# MCB-Laird-BL652-v2_0_0.net
KiCad netlist of a schematic drawn in EAGLE
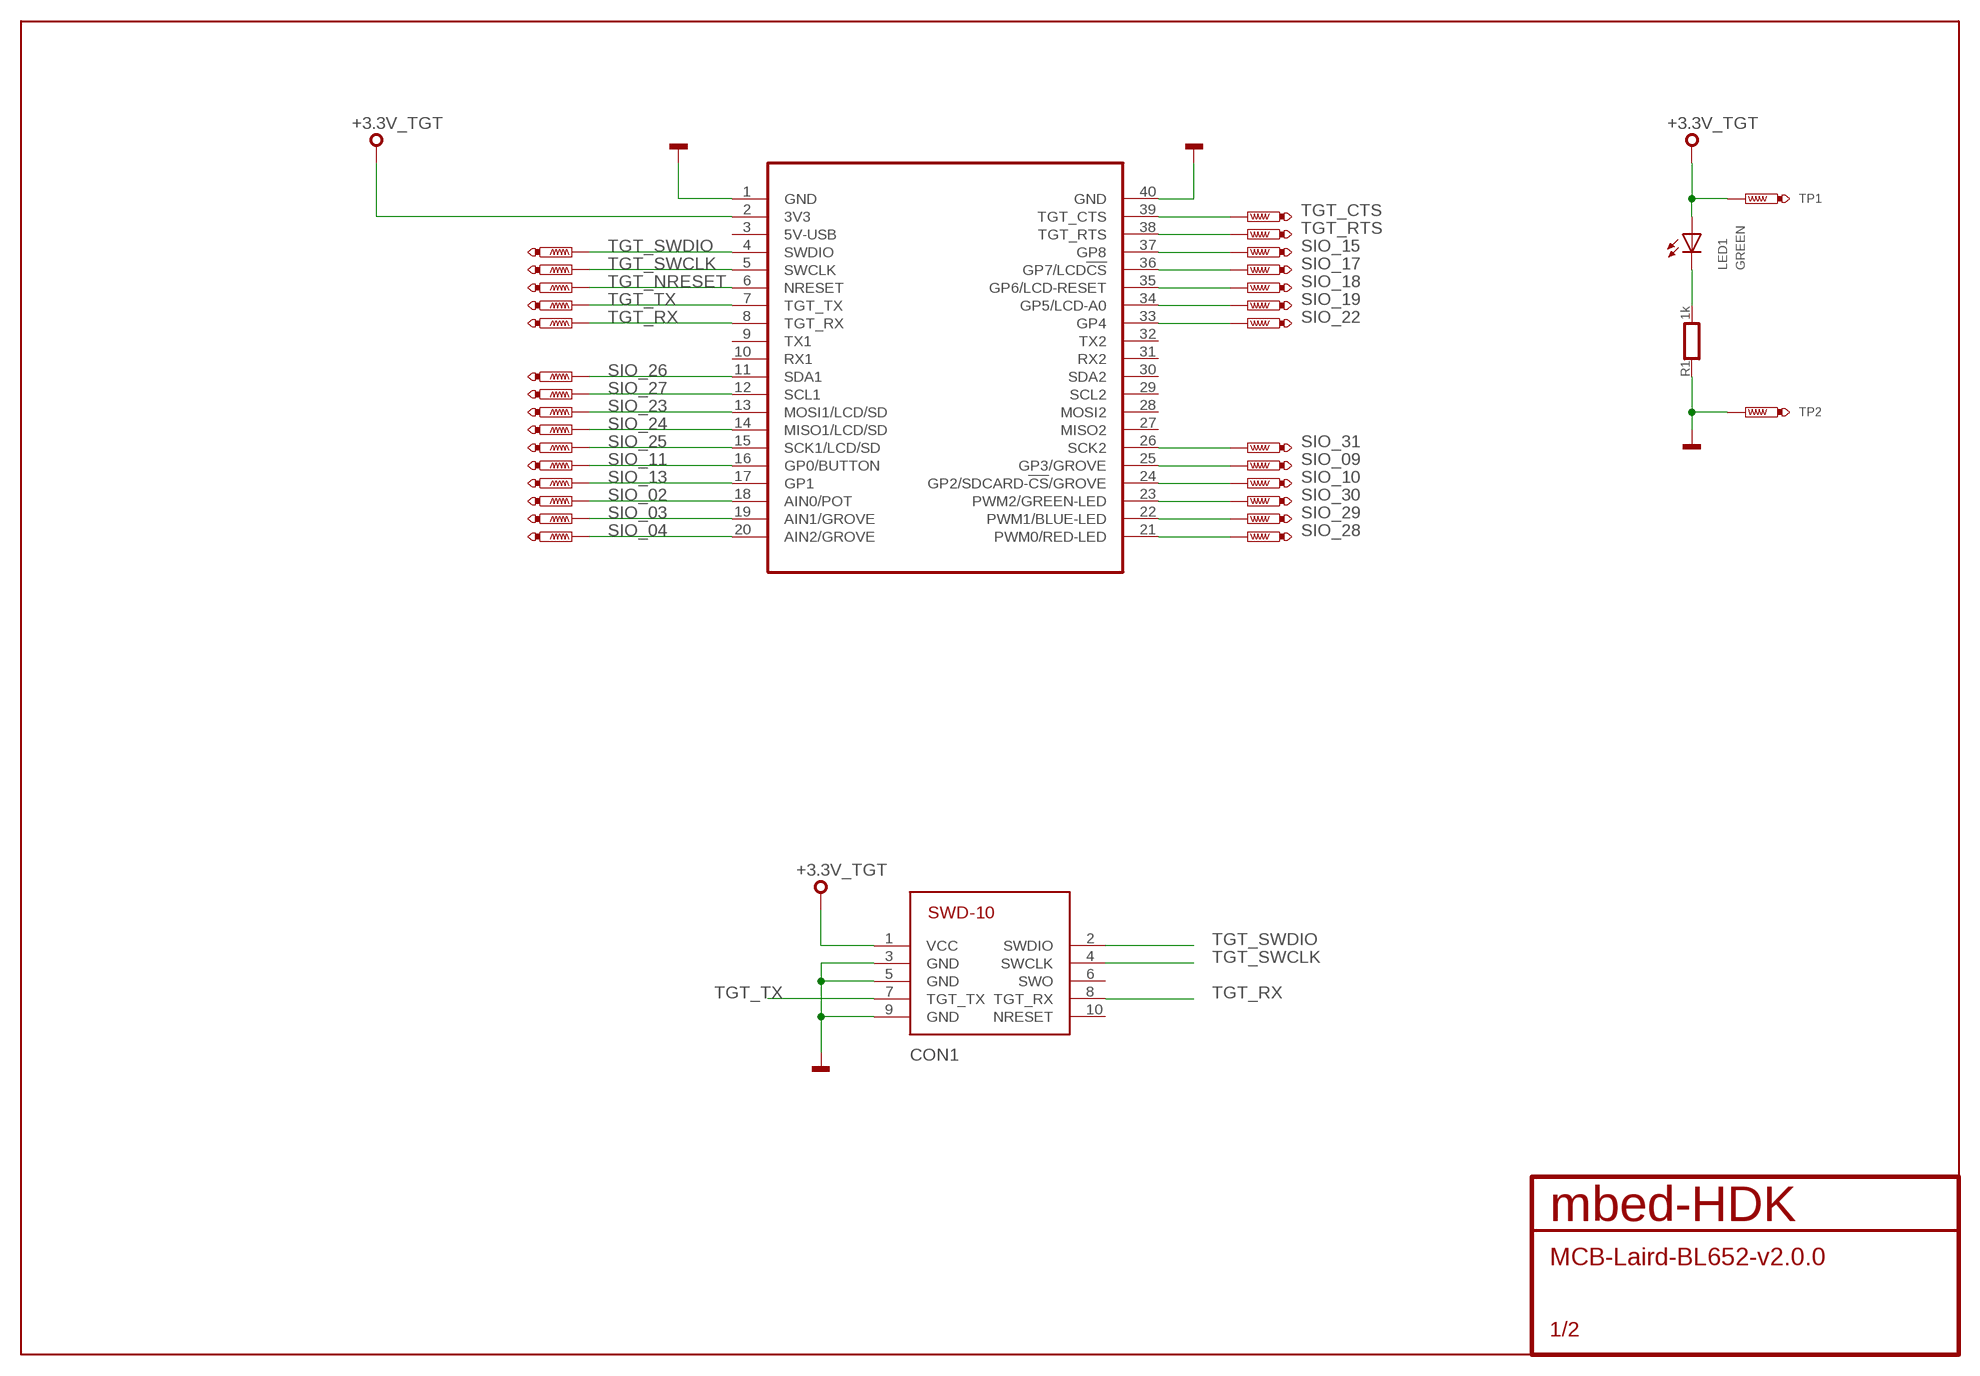
[diagram p0: schematic, sheet 1]
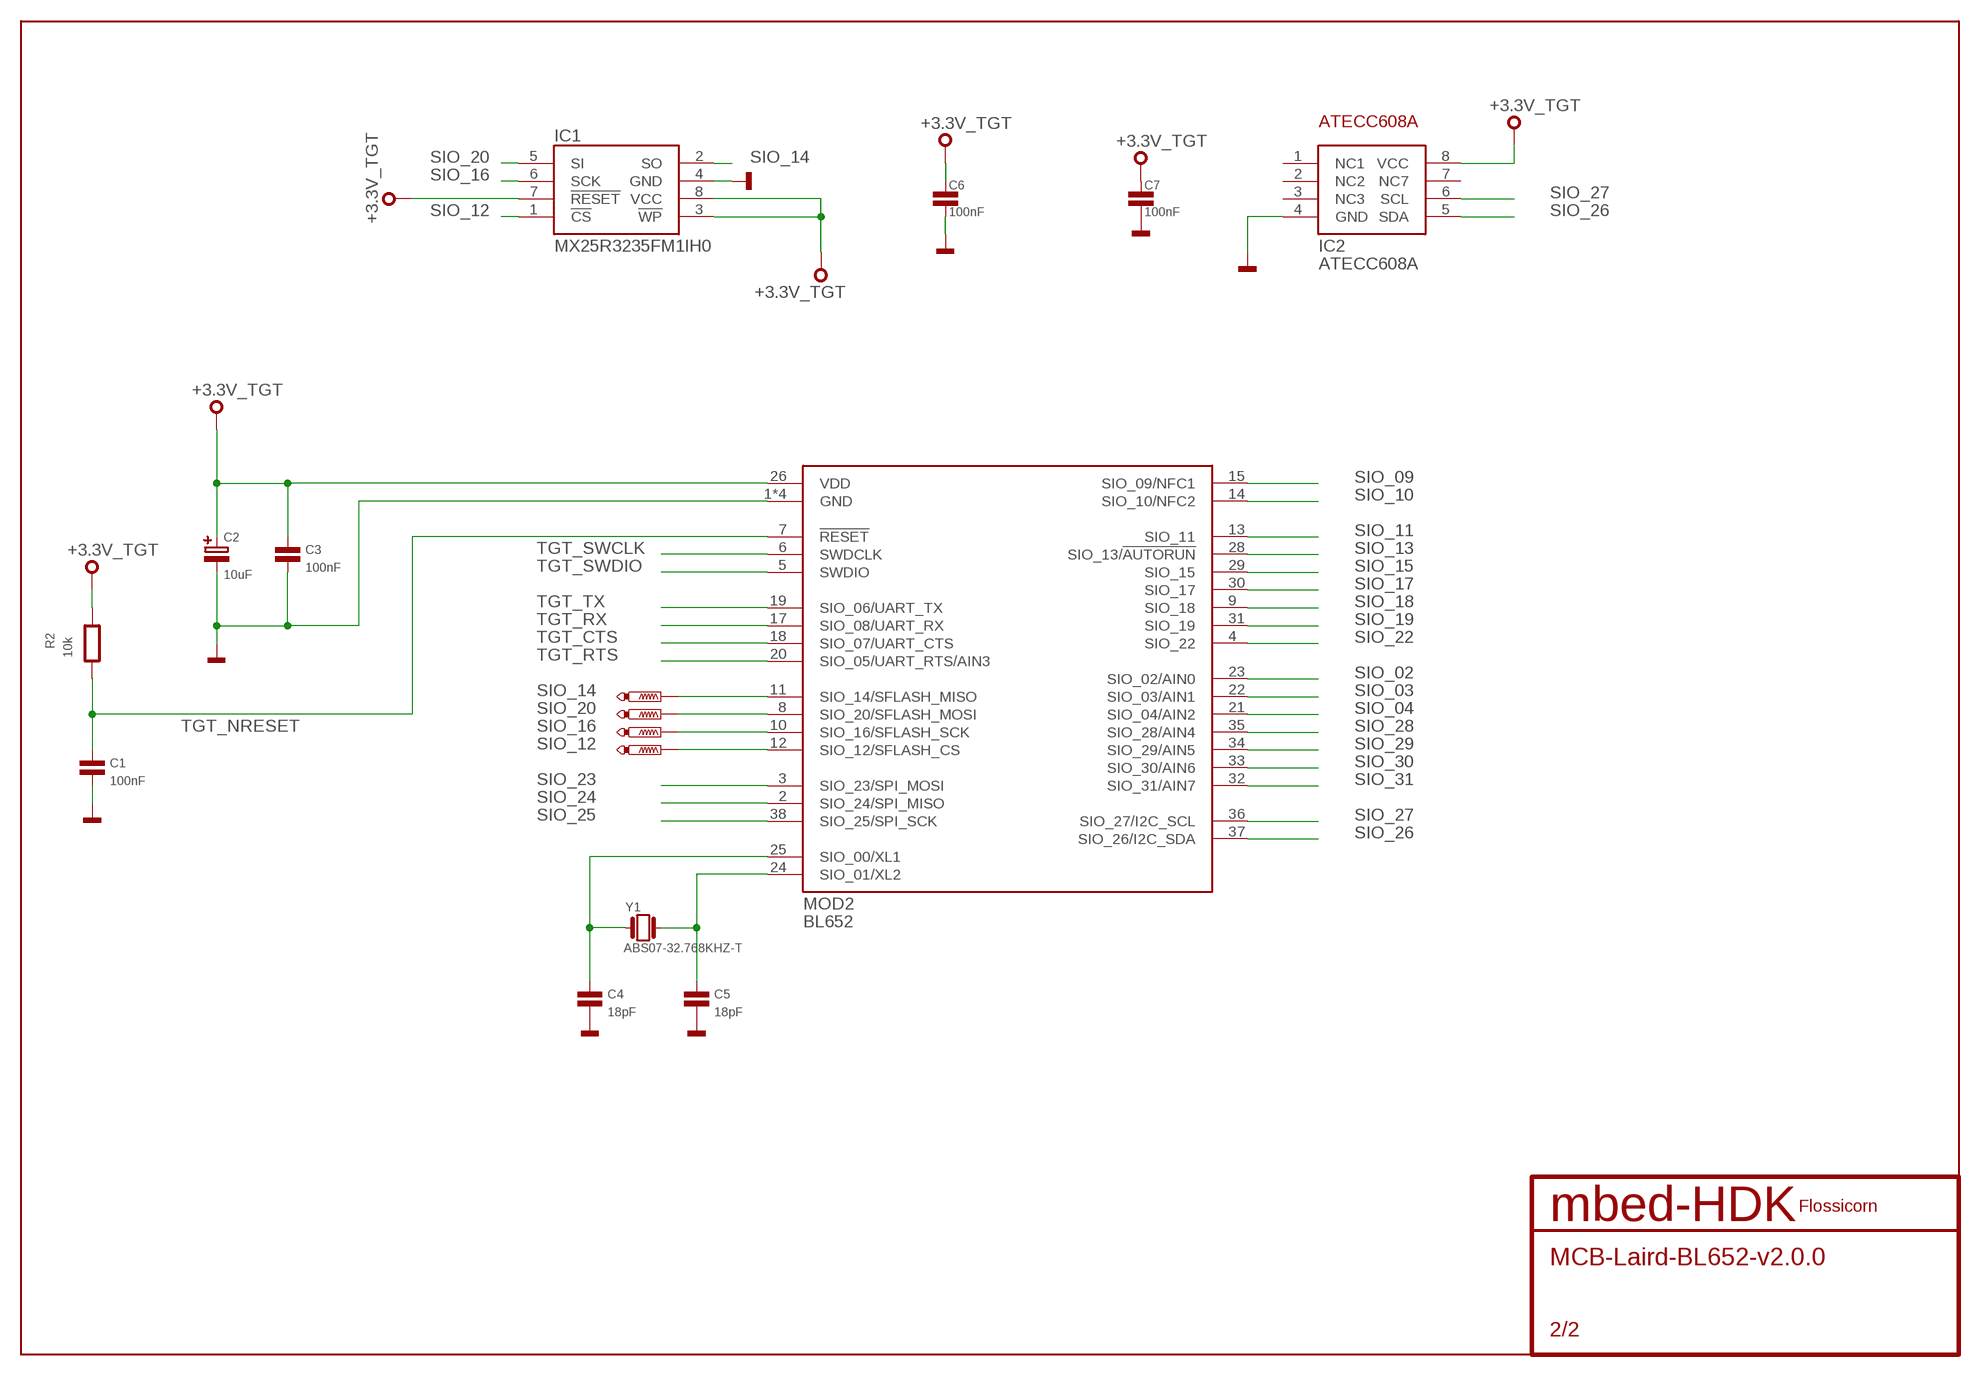
[diagram p1: schematic, sheet 2]

(export (version "E")
  (design (tool "Eeschema 10.0.6"))
  (components
    (comp (ref "CON1")
      (value "SWD-10/TC2050_SMD")
      (footprint "eagle-import:FTSH-105-02")
      (libsource (lib "eagle-import") (part "SWD-10/TC2050_SMD"))
    )
    (comp (ref "LED1")
      (value "GREEN")
      (footprint "eagle-import:CHIPLED_0603")
      (fields (field (name "MF") "Wurth Electronics Inc"))
      (libsource (lib "eagle-import") (part "SMD_LED0603"))
    )
    (comp (ref "MOD1")
      (value "MODULE_DAUGHTER")
      (footprint "eagle-import:MODULE_DAUGHTER")
      (libsource (lib "eagle-import") (part "MODULE_DAUGHTER"))
    )
    (comp (ref "R1")
      (value "1k")
      (footprint "eagle-import:0603")
      (libsource (lib "eagle-import") (part "RESISTOR0603"))
    )
    (comp (ref "TP1")
      (value "TEST-POINT-50R-PTH")
      (footprint "eagle-import:TP50-PTH")
      (libsource (lib "eagle-import") (part "TEST-POINT-50R-PTH"))
    )
    (comp (ref "TP2")
      (value "TEST-POINT-50R-PTH")
      (footprint "eagle-import:TP50-PTH")
      (libsource (lib "eagle-import") (part "TEST-POINT-50R-PTH"))
    )
    (comp (ref "TP3")
      (value "PTR1TP07R")
      (footprint "eagle-import:TP07R")
      (libsource (lib "eagle-import") (part "PTR1TP07R"))
    )
    (comp (ref "TP4")
      (value "PTR1TP07R")
      (footprint "eagle-import:TP07R")
      (libsource (lib "eagle-import") (part "PTR1TP07R"))
    )
    (comp (ref "TP5")
      (value "PTR1TP07R")
      (footprint "eagle-import:TP07R")
      (libsource (lib "eagle-import") (part "PTR1TP07R"))
    )
    (comp (ref "TP6")
      (value "PTR1TP07R")
      (footprint "eagle-import:TP07R")
      (libsource (lib "eagle-import") (part "PTR1TP07R"))
    )
    (comp (ref "TP7")
      (value "PTR1TP07R")
      (footprint "eagle-import:TP07R")
      (libsource (lib "eagle-import") (part "PTR1TP07R"))
    )
    (comp (ref "TP8")
      (value "PTR1TP07R")
      (footprint "eagle-import:TP07R")
      (libsource (lib "eagle-import") (part "PTR1TP07R"))
    )
    (comp (ref "TP9")
      (value "PTR1TP07R")
      (footprint "eagle-import:TP07R")
      (libsource (lib "eagle-import") (part "PTR1TP07R"))
    )
    (comp (ref "TP10")
      (value "PTR1TP07R")
      (footprint "eagle-import:TP07R")
      (libsource (lib "eagle-import") (part "PTR1TP07R"))
    )
    (comp (ref "TP11")
      (value "PTR1TP07R")
      (footprint "eagle-import:TP07R")
      (libsource (lib "eagle-import") (part "PTR1TP07R"))
    )
    (comp (ref "TP12")
      (value "PTR1TP07R")
      (footprint "eagle-import:TP07R")
      (libsource (lib "eagle-import") (part "PTR1TP07R"))
    )
    (comp (ref "TP13")
      (value "PTR1TP07R")
      (footprint "eagle-import:TP07R")
      (libsource (lib "eagle-import") (part "PTR1TP07R"))
    )
    (comp (ref "TP14")
      (value "PTR1TP07R")
      (footprint "eagle-import:TP07R")
      (libsource (lib "eagle-import") (part "PTR1TP07R"))
    )
    (comp (ref "TP15")
      (value "PTR1TP07R")
      (footprint "eagle-import:TP07R")
      (libsource (lib "eagle-import") (part "PTR1TP07R"))
    )
    (comp (ref "TP16")
      (value "PTR1TP07R")
      (footprint "eagle-import:TP07R")
      (libsource (lib "eagle-import") (part "PTR1TP07R"))
    )
    (comp (ref "TP17")
      (value "PTR1TP07R")
      (footprint "eagle-import:TP07R")
      (libsource (lib "eagle-import") (part "PTR1TP07R"))
    )
    (comp (ref "TP18")
      (value "PTR1TP07R")
      (footprint "eagle-import:TP07R")
      (libsource (lib "eagle-import") (part "PTR1TP07R"))
    )
    (comp (ref "TP19")
      (value "PTR1TP07R")
      (footprint "eagle-import:TP07R")
      (libsource (lib "eagle-import") (part "PTR1TP07R"))
    )
    (comp (ref "TP20")
      (value "PTR1TP07R")
      (footprint "eagle-import:TP07R")
      (libsource (lib "eagle-import") (part "PTR1TP07R"))
    )
    (comp (ref "TP21")
      (value "PTR1TP07R")
      (footprint "eagle-import:TP07R")
      (libsource (lib "eagle-import") (part "PTR1TP07R"))
    )
    (comp (ref "TP22")
      (value "PTR1TP07R")
      (footprint "eagle-import:TP07R")
      (libsource (lib "eagle-import") (part "PTR1TP07R"))
    )
    (comp (ref "TP23")
      (value "PTR1TP07R")
      (footprint "eagle-import:TP07R")
      (libsource (lib "eagle-import") (part "PTR1TP07R"))
    )
    (comp (ref "TP24")
      (value "PTR1TP07R")
      (footprint "eagle-import:TP07R")
      (libsource (lib "eagle-import") (part "PTR1TP07R"))
    )
    (comp (ref "TP25")
      (value "PTR1TP07R")
      (footprint "eagle-import:TP07R")
      (libsource (lib "eagle-import") (part "PTR1TP07R"))
    )
    (comp (ref "TP26")
      (value "PTR1TP07R")
      (footprint "eagle-import:TP07R")
      (libsource (lib "eagle-import") (part "PTR1TP07R"))
    )
    (comp (ref "TP27")
      (value "PTR1TP07R")
      (footprint "eagle-import:TP07R")
      (libsource (lib "eagle-import") (part "PTR1TP07R"))
    )
    (comp (ref "TP28")
      (value "PTR1TP07R")
      (footprint "eagle-import:TP07R")
      (libsource (lib "eagle-import") (part "PTR1TP07R"))
    )
    (comp (ref "TP29")
      (value "PTR1TP07R")
      (footprint "eagle-import:TP07R")
      (libsource (lib "eagle-import") (part "PTR1TP07R"))
    )
    (comp (ref "TP30")
      (value "PTR1TP07R")
      (footprint "eagle-import:TP07R")
      (libsource (lib "eagle-import") (part "PTR1TP07R"))
    )
    (comp (ref "C1")
      (value "100nF")
      (footprint "eagle-import:0603")
      (libsource (lib "eagle-import") (part "C0603"))
    )
    (comp (ref "C2")
      (value "10uF")
      (footprint "eagle-import:SMC_B")
      (fields (field (name "MF") "Kemet"))
      (libsource (lib "eagle-import") (part "CAPACITOR-POLARISEDB"))
    )
    (comp (ref "C3")
      (value "100nF")
      (footprint "eagle-import:0603")
      (libsource (lib "eagle-import") (part "C0603"))
    )
    (comp (ref "C4")
      (value "18pF")
      (footprint "eagle-import:0603")
      (libsource (lib "eagle-import") (part "C0603"))
    )
    (comp (ref "C5")
      (value "18pF")
      (footprint "eagle-import:0603")
      (libsource (lib "eagle-import") (part "C0603"))
    )
    (comp (ref "C6")
      (value "100nF")
      (footprint "eagle-import:0603")
      (libsource (lib "eagle-import") (part "CAPACITOR0603"))
    )
    (comp (ref "C7")
      (value "100nF")
      (footprint "eagle-import:0603")
      (libsource (lib "eagle-import") (part "CAPACITOR0603"))
    )
    (comp (ref "IC1")
      (value "MX25R3235FM1IH0")
      (footprint "eagle-import:SO8")
      (fields (field (name "MF") "Macronix"))
      (libsource (lib "eagle-import") (part "MX25R3235FM1IH0"))
    )
    (comp (ref "IC2")
      (value "ATECC608A")
      (footprint "eagle-import:SO8")
      (fields (field (name "MF") "Atmel"))
      (libsource (lib "eagle-import") (part "ATECC608A"))
    )
    (comp (ref "MOD2")
      (value "BL652")
      (footprint "eagle-import:BL652")
      (fields (field (name "MF") "Laird"))
      (libsource (lib "eagle-import") (part "BL652"))
    )
    (comp (ref "R2")
      (value "10k")
      (footprint "eagle-import:0603")
      (libsource (lib "eagle-import") (part "RESISTOR0603"))
    )
    (comp (ref "SS1")
      (value "FLOSSICORN0.25")
      (footprint "eagle-import:FLOSSICORN-0.25")
      (libsource (lib "eagle-import") (part "FLOSSICORN0.25"))
    )
    (comp (ref "TP31")
      (value "PTR1TP07R")
      (footprint "eagle-import:TP07R")
      (libsource (lib "eagle-import") (part "PTR1TP07R"))
    )
    (comp (ref "TP32")
      (value "PTR1TP07R")
      (footprint "eagle-import:TP07R")
      (libsource (lib "eagle-import") (part "PTR1TP07R"))
    )
    (comp (ref "TP33")
      (value "PTR1TP07R")
      (footprint "eagle-import:TP07R")
      (libsource (lib "eagle-import") (part "PTR1TP07R"))
    )
    (comp (ref "TP34")
      (value "PTR1TP07R")
      (footprint "eagle-import:TP07R")
      (libsource (lib "eagle-import") (part "PTR1TP07R"))
    )
    (comp (ref "Y1")
      (value "ABS07-32.768KHZ-T")
      (footprint "eagle-import:FC135")
      (fields (field (name "MF") "Abracon"))
      (libsource (lib "eagle-import") (part "ABS07-32.768KHZ-T"))
    )
  )
  (nets
    (net (code "1") (name "+3.3V_TGT") (class "Default")
      (node (ref "C2") (pin "+") (pinfunction "+_+") (pintype "passive"))
      (node (ref "C3") (pin "1") (pinfunction "P$1_1") (pintype "passive"))
      (node (ref "C6") (pin "1") (pinfunction "P$1_1") (pintype "passive"))
      (node (ref "C7") (pin "1") (pinfunction "P$1_1") (pintype "passive"))
      (node (ref "CON1") (pin "1") (pinfunction "VCC_1") (pintype "bidirectional"))
      (node (ref "IC1") (pin "3") (pinfunction "~{WP}_3") (pintype "bidirectional"))
      (node (ref "IC1") (pin "7") (pinfunction "~{RESET}_7") (pintype "bidirectional"))
      (node (ref "IC1") (pin "8") (pinfunction "VCC_8") (pintype "bidirectional"))
      (node (ref "IC2") (pin "8") (pinfunction "VCC_8") (pintype "bidirectional"))
      (node (ref "LED1") (pin "A") (pinfunction "A_A") (pintype "passive"))
      (node (ref "MOD1") (pin "2") (pinfunction "3V3_2") (pintype "bidirectional"))
      (node (ref "MOD2") (pin "26") (pinfunction "VDD_26") (pintype "bidirectional"))
      (node (ref "R2") (pin "2") (pinfunction "P$2_2") (pintype "passive"))
      (node (ref "TP1") (pin "TP") (pinfunction "TP_TP") (pintype "input"))
    )
    (net (code "2") (name "GND") (class "Default")
      (node (ref "C1") (pin "2") (pinfunction "P$2_2") (pintype "passive"))
      (node (ref "C2") (pin "-") (pinfunction "-_-") (pintype "passive"))
      (node (ref "C3") (pin "2") (pinfunction "P$2_2") (pintype "passive"))
      (node (ref "C4") (pin "2") (pinfunction "P$2_2") (pintype "passive"))
      (node (ref "C5") (pin "2") (pinfunction "P$2_2") (pintype "passive"))
      (node (ref "C6") (pin "2") (pinfunction "P$2_2") (pintype "passive"))
      (node (ref "C7") (pin "2") (pinfunction "P$2_2") (pintype "passive"))
      (node (ref "CON1") (pin "3") (pinfunction "GND_3") (pintype "bidirectional"))
      (node (ref "CON1") (pin "5") (pinfunction "GND_5") (pintype "bidirectional"))
      (node (ref "CON1") (pin "9") (pinfunction "GND_9") (pintype "bidirectional"))
      (node (ref "IC1") (pin "4") (pinfunction "GND_4") (pintype "bidirectional"))
      (node (ref "IC2") (pin "4") (pinfunction "GND_4") (pintype "bidirectional"))
      (node (ref "MOD1") (pin "1") (pinfunction "GND_1") (pintype "bidirectional"))
      (node (ref "MOD1") (pin "40") (pinfunction "GND_40") (pintype "bidirectional"))
      (node (ref "MOD2") (pin "1") (pinfunction "GND_1") (pintype "bidirectional"))
      (node (ref "MOD2") (pin "16") (pinfunction "GND_16") (pintype "bidirectional"))
      (node (ref "MOD2") (pin "27") (pinfunction "GND_27") (pintype "bidirectional"))
      (node (ref "MOD2") (pin "39") (pinfunction "GND_39") (pintype "bidirectional"))
      (node (ref "R1") (pin "1") (pinfunction "P$1_1") (pintype "passive"))
      (node (ref "TP2") (pin "TP") (pinfunction "TP_TP") (pintype "input"))
    )
    (net (code "3") (name "Net-(C4-P$1)") (class "Default")
      (node (ref "C4") (pin "1") (pinfunction "P$1_1") (pintype "passive"))
      (node (ref "MOD2") (pin "25") (pinfunction "SIO_00/XL1_25") (pintype "bidirectional"))
      (node (ref "Y1") (pin "X1") (pinfunction "1_X1") (pintype "passive"))
    )
    (net (code "4") (name "Net-(C5-P$1)") (class "Default")
      (node (ref "C5") (pin "1") (pinfunction "P$1_1") (pintype "passive"))
      (node (ref "MOD2") (pin "24") (pinfunction "SIO_01/XL2_24") (pintype "bidirectional"))
      (node (ref "Y1") (pin "X2") (pinfunction "2_X2") (pintype "passive"))
    )
    (net (code "5") (name "Net-(R1-P$2)") (class "Default")
      (node (ref "LED1") (pin "C") (pinfunction "C_C") (pintype "passive"))
      (node (ref "R1") (pin "2") (pinfunction "P$2_2") (pintype "passive"))
    )
    (net (code "6") (name "SIO_02") (class "Default")
      (node (ref "MOD1") (pin "18") (pinfunction "AIN0/POT_18") (pintype "bidirectional"))
      (node (ref "MOD2") (pin "23") (pinfunction "SIO_02/AIN0_23") (pintype "bidirectional"))
      (node (ref "TP10") (pin "TP") (pinfunction "TP_TP") (pintype "input"))
    )
    (net (code "7") (name "SIO_03") (class "Default")
      (node (ref "MOD1") (pin "19") (pinfunction "AIN1/GROVE_19") (pintype "bidirectional"))
      (node (ref "MOD2") (pin "22") (pinfunction "SIO_03/AIN1_22") (pintype "bidirectional"))
      (node (ref "TP11") (pin "TP") (pinfunction "TP_TP") (pintype "input"))
    )
    (net (code "8") (name "SIO_04") (class "Default")
      (node (ref "MOD1") (pin "20") (pinfunction "AIN2/GROVE_20") (pintype "bidirectional"))
      (node (ref "MOD2") (pin "21") (pinfunction "SIO_04/AIN2_21") (pintype "bidirectional"))
      (node (ref "TP12") (pin "TP") (pinfunction "TP_TP") (pintype "input"))
    )
    (net (code "9") (name "SIO_09") (class "Default")
      (node (ref "MOD1") (pin "25") (pinfunction "GP3/GROVE_25") (pintype "bidirectional"))
      (node (ref "MOD2") (pin "15") (pinfunction "SIO_09/NFC1_15") (pintype "bidirectional"))
      (node (ref "TP17") (pin "TP") (pinfunction "TP_TP") (pintype "input"))
    )
    (net (code "10") (name "SIO_10") (class "Default")
      (node (ref "MOD1") (pin "24") (pinfunction "GP2/SDCARD-~{CS}/GROVE_24") (pintype "bidirectional"))
      (node (ref "MOD2") (pin "14") (pinfunction "SIO_10/NFC2_14") (pintype "bidirectional"))
      (node (ref "TP16") (pin "TP") (pinfunction "TP_TP") (pintype "input"))
    )
    (net (code "11") (name "SIO_11") (class "Default")
      (node (ref "MOD1") (pin "16") (pinfunction "GP0/BUTTON_16") (pintype "bidirectional"))
      (node (ref "MOD2") (pin "13") (pinfunction "SIO_11_13") (pintype "bidirectional"))
      (node (ref "TP8") (pin "TP") (pinfunction "TP_TP") (pintype "input"))
    )
    (net (code "12") (name "SIO_12") (class "Default")
      (node (ref "IC1") (pin "1") (pinfunction "~{CS}_1") (pintype "bidirectional"))
      (node (ref "MOD2") (pin "12") (pinfunction "SIO_12/SFLASH_CS_12") (pintype "bidirectional"))
      (node (ref "TP34") (pin "TP") (pinfunction "TP_TP") (pintype "input"))
    )
    (net (code "13") (name "SIO_13") (class "Default")
      (node (ref "MOD1") (pin "17") (pinfunction "GP1_17") (pintype "bidirectional"))
      (node (ref "MOD2") (pin "28") (pinfunction "SIO_13/~{AUTORUN}_28") (pintype "bidirectional"))
      (node (ref "TP9") (pin "TP") (pinfunction "TP_TP") (pintype "input"))
    )
    (net (code "14") (name "SIO_14") (class "Default")
      (node (ref "IC1") (pin "2") (pinfunction "SO_2") (pintype "bidirectional"))
      (node (ref "MOD2") (pin "11") (pinfunction "SIO_14/SFLASH_MISO_11") (pintype "bidirectional"))
      (node (ref "TP31") (pin "TP") (pinfunction "TP_TP") (pintype "input"))
    )
    (net (code "15") (name "SIO_15") (class "Default")
      (node (ref "MOD1") (pin "37") (pinfunction "GP8_37") (pintype "bidirectional"))
      (node (ref "MOD2") (pin "29") (pinfunction "SIO_15_29") (pintype "bidirectional"))
      (node (ref "TP22") (pin "TP") (pinfunction "TP_TP") (pintype "input"))
    )
    (net (code "16") (name "SIO_16") (class "Default")
      (node (ref "IC1") (pin "6") (pinfunction "SCK_6") (pintype "bidirectional"))
      (node (ref "MOD2") (pin "10") (pinfunction "SIO_16/SFLASH_SCK_10") (pintype "bidirectional"))
      (node (ref "TP33") (pin "TP") (pinfunction "TP_TP") (pintype "input"))
    )
    (net (code "17") (name "SIO_17") (class "Default")
      (node (ref "MOD1") (pin "36") (pinfunction "GP7/LCD~{CS}_36") (pintype "bidirectional"))
      (node (ref "MOD2") (pin "30") (pinfunction "SIO_17_30") (pintype "bidirectional"))
      (node (ref "TP21") (pin "TP") (pinfunction "TP_TP") (pintype "input"))
    )
    (net (code "18") (name "SIO_18") (class "Default")
      (node (ref "MOD1") (pin "35") (pinfunction "GP6/LCD-RESET_35") (pintype "bidirectional"))
      (node (ref "MOD2") (pin "9") (pinfunction "SIO_18_9") (pintype "bidirectional"))
      (node (ref "TP20") (pin "TP") (pinfunction "TP_TP") (pintype "input"))
    )
    (net (code "19") (name "SIO_19") (class "Default")
      (node (ref "MOD1") (pin "34") (pinfunction "GP5/LCD-A0_34") (pintype "bidirectional"))
      (node (ref "MOD2") (pin "31") (pinfunction "SIO_19_31") (pintype "bidirectional"))
      (node (ref "TP19") (pin "TP") (pinfunction "TP_TP") (pintype "input"))
    )
    (net (code "20") (name "SIO_20") (class "Default")
      (node (ref "IC1") (pin "5") (pinfunction "SI_5") (pintype "bidirectional"))
      (node (ref "MOD2") (pin "8") (pinfunction "SIO_20/SFLASH_MOSI_8") (pintype "bidirectional"))
      (node (ref "TP32") (pin "TP") (pinfunction "TP_TP") (pintype "input"))
    )
    (net (code "21") (name "SIO_22") (class "Default")
      (node (ref "MOD1") (pin "33") (pinfunction "GP4_33") (pintype "bidirectional"))
      (node (ref "MOD2") (pin "4") (pinfunction "SIO_22_4") (pintype "bidirectional"))
      (node (ref "TP18") (pin "TP") (pinfunction "TP_TP") (pintype "input"))
    )
    (net (code "22") (name "SIO_23") (class "Default")
      (node (ref "MOD1") (pin "13") (pinfunction "MOSI1/LCD/SD_13") (pintype "bidirectional"))
      (node (ref "MOD2") (pin "3") (pinfunction "SIO_23/SPI_MOSI_3") (pintype "bidirectional"))
      (node (ref "TP5") (pin "TP") (pinfunction "TP_TP") (pintype "input"))
    )
    (net (code "23") (name "SIO_24") (class "Default")
      (node (ref "MOD1") (pin "14") (pinfunction "MISO1/LCD/SD_14") (pintype "bidirectional"))
      (node (ref "MOD2") (pin "2") (pinfunction "SIO_24/SPI_MISO_2") (pintype "bidirectional"))
      (node (ref "TP6") (pin "TP") (pinfunction "TP_TP") (pintype "input"))
    )
    (net (code "24") (name "SIO_25") (class "Default")
      (node (ref "MOD1") (pin "15") (pinfunction "SCK1/LCD/SD_15") (pintype "bidirectional"))
      (node (ref "MOD2") (pin "38") (pinfunction "SIO_25/SPI_SCK_38") (pintype "bidirectional"))
      (node (ref "TP7") (pin "TP") (pinfunction "TP_TP") (pintype "input"))
    )
    (net (code "25") (name "SIO_26") (class "Default")
      (node (ref "IC2") (pin "5") (pinfunction "SDA_5") (pintype "bidirectional"))
      (node (ref "MOD1") (pin "11") (pinfunction "SDA1_11") (pintype "bidirectional"))
      (node (ref "MOD2") (pin "37") (pinfunction "SIO_26/I2C_SDA_37") (pintype "bidirectional"))
      (node (ref "TP3") (pin "TP") (pinfunction "TP_TP") (pintype "input"))
    )
    (net (code "26") (name "SIO_27") (class "Default")
      (node (ref "IC2") (pin "6") (pinfunction "SCL_6") (pintype "bidirectional"))
      (node (ref "MOD1") (pin "12") (pinfunction "SCL1_12") (pintype "bidirectional"))
      (node (ref "MOD2") (pin "36") (pinfunction "SIO_27/I2C_SCL_36") (pintype "bidirectional"))
      (node (ref "TP4") (pin "TP") (pinfunction "TP_TP") (pintype "input"))
    )
    (net (code "27") (name "SIO_28") (class "Default")
      (node (ref "MOD1") (pin "21") (pinfunction "PWM0/RED-LED_21") (pintype "bidirectional"))
      (node (ref "MOD2") (pin "35") (pinfunction "SIO_28/AIN4_35") (pintype "bidirectional"))
      (node (ref "TP13") (pin "TP") (pinfunction "TP_TP") (pintype "input"))
    )
    (net (code "28") (name "SIO_29") (class "Default")
      (node (ref "MOD1") (pin "22") (pinfunction "PWM1/BLUE-LED_22") (pintype "bidirectional"))
      (node (ref "MOD2") (pin "34") (pinfunction "SIO_29/AIN5_34") (pintype "bidirectional"))
      (node (ref "TP14") (pin "TP") (pinfunction "TP_TP") (pintype "input"))
    )
    (net (code "29") (name "SIO_30") (class "Default")
      (node (ref "MOD1") (pin "23") (pinfunction "PWM2/GREEN-LED_23") (pintype "bidirectional"))
      (node (ref "MOD2") (pin "33") (pinfunction "SIO_30/AIN6_33") (pintype "bidirectional"))
      (node (ref "TP15") (pin "TP") (pinfunction "TP_TP") (pintype "input"))
    )
    (net (code "30") (name "SIO_31") (class "Default")
      (node (ref "MOD1") (pin "26") (pinfunction "SCK2_26") (pintype "bidirectional"))
      (node (ref "MOD2") (pin "32") (pinfunction "SIO_31/AIN7_32") (pintype "bidirectional"))
      (node (ref "TP25") (pin "TP") (pinfunction "TP_TP") (pintype "input"))
    )
    (net (code "31") (name "TGT_CTS") (class "Default")
      (node (ref "MOD1") (pin "39") (pinfunction "TGT_CTS_39") (pintype "bidirectional"))
      (node (ref "MOD2") (pin "18") (pinfunction "SIO_07/UART_CTS_18") (pintype "bidirectional"))
      (node (ref "TP24") (pin "TP") (pinfunction "TP_TP") (pintype "input"))
    )
    (net (code "32") (name "TGT_NRESET") (class "Default")
      (node (ref "C1") (pin "1") (pinfunction "P$1_1") (pintype "passive"))
      (node (ref "MOD1") (pin "6") (pinfunction "NRESET_6") (pintype "bidirectional"))
      (node (ref "MOD2") (pin "7") (pinfunction "~{RESET}_7") (pintype "bidirectional"))
      (node (ref "R2") (pin "1") (pinfunction "P$1_1") (pintype "passive"))
      (node (ref "TP28") (pin "TP") (pinfunction "TP_TP") (pintype "input"))
    )
    (net (code "33") (name "TGT_RTS") (class "Default")
      (node (ref "MOD1") (pin "38") (pinfunction "TGT_RTS_38") (pintype "bidirectional"))
      (node (ref "MOD2") (pin "20") (pinfunction "SIO_05/UART_RTS/AIN3_20") (pintype "bidirectional"))
      (node (ref "TP23") (pin "TP") (pinfunction "TP_TP") (pintype "input"))
    )
    (net (code "34") (name "TGT_RX") (class "Default")
      (node (ref "CON1") (pin "8") (pinfunction "TGT_RX_8") (pintype "bidirectional"))
      (node (ref "MOD1") (pin "8") (pinfunction "TGT_RX_8") (pintype "bidirectional"))
      (node (ref "MOD2") (pin "17") (pinfunction "SIO_08/UART_RX_17") (pintype "bidirectional"))
      (node (ref "TP30") (pin "TP") (pinfunction "TP_TP") (pintype "input"))
    )
    (net (code "35") (name "TGT_SWCLK") (class "Default")
      (node (ref "CON1") (pin "4") (pinfunction "SWCLK_4") (pintype "bidirectional"))
      (node (ref "MOD1") (pin "5") (pinfunction "SWCLK_5") (pintype "bidirectional"))
      (node (ref "MOD2") (pin "6") (pinfunction "SWDCLK_6") (pintype "bidirectional"))
      (node (ref "TP27") (pin "TP") (pinfunction "TP_TP") (pintype "input"))
    )
    (net (code "36") (name "TGT_SWDIO") (class "Default")
      (node (ref "CON1") (pin "2") (pinfunction "SWDIO_2") (pintype "bidirectional"))
      (node (ref "MOD1") (pin "4") (pinfunction "SWDIO_4") (pintype "bidirectional"))
      (node (ref "MOD2") (pin "5") (pinfunction "SWDIO_5") (pintype "bidirectional"))
      (node (ref "TP26") (pin "TP") (pinfunction "TP_TP") (pintype "input"))
    )
    (net (code "37") (name "TGT_TX") (class "Default")
      (node (ref "CON1") (pin "7") (pinfunction "TGT_TX_7") (pintype "bidirectional"))
      (node (ref "MOD1") (pin "7") (pinfunction "TGT_TX_7") (pintype "bidirectional"))
      (node (ref "MOD2") (pin "19") (pinfunction "SIO_06/UART_TX_19") (pintype "bidirectional"))
      (node (ref "TP29") (pin "TP") (pinfunction "TP_TP") (pintype "input"))
    )
    (net (code "38") (name "unconnected-(CON1-NRESET-Pad10)") (class "Default")
      (node (ref "CON1") (pin "10") (pinfunction "NRESET_10") (pintype "bidirectional"))
    )
    (net (code "39") (name "unconnected-(CON1-SWO-Pad6)") (class "Default")
      (node (ref "CON1") (pin "6") (pinfunction "SWO_6") (pintype "bidirectional"))
    )
    (net (code "40") (name "unconnected-(IC2-NC1-Pad1)") (class "Default")
      (node (ref "IC2") (pin "1") (pinfunction "NC1_1") (pintype "bidirectional"))
    )
    (net (code "41") (name "unconnected-(IC2-NC2-Pad2)") (class "Default")
      (node (ref "IC2") (pin "2") (pinfunction "NC2_2") (pintype "bidirectional"))
    )
    (net (code "42") (name "unconnected-(IC2-NC3-Pad3)") (class "Default")
      (node (ref "IC2") (pin "3") (pinfunction "NC3_3") (pintype "bidirectional"))
    )
    (net (code "43") (name "unconnected-(IC2-NC7-Pad7)") (class "Default")
      (node (ref "IC2") (pin "7") (pinfunction "NC7_7") (pintype "bidirectional"))
    )
    (net (code "44") (name "unconnected-(MOD1-5V-USB-Pad3)") (class "Default")
      (node (ref "MOD1") (pin "3") (pinfunction "5V-USB_3") (pintype "bidirectional"))
    )
    (net (code "45") (name "unconnected-(MOD1-MISO2-Pad27)") (class "Default")
      (node (ref "MOD1") (pin "27") (pinfunction "MISO2_27") (pintype "bidirectional"))
    )
    (net (code "46") (name "unconnected-(MOD1-MOSI2-Pad28)") (class "Default")
      (node (ref "MOD1") (pin "28") (pinfunction "MOSI2_28") (pintype "bidirectional"))
    )
    (net (code "47") (name "unconnected-(MOD1-RX1-Pad10)") (class "Default")
      (node (ref "MOD1") (pin "10") (pinfunction "RX1_10") (pintype "bidirectional"))
    )
    (net (code "48") (name "unconnected-(MOD1-RX2-Pad31)") (class "Default")
      (node (ref "MOD1") (pin "31") (pinfunction "RX2_31") (pintype "bidirectional"))
    )
    (net (code "49") (name "unconnected-(MOD1-SCL2-Pad29)") (class "Default")
      (node (ref "MOD1") (pin "29") (pinfunction "SCL2_29") (pintype "bidirectional"))
    )
    (net (code "50") (name "unconnected-(MOD1-SDA2-Pad30)") (class "Default")
      (node (ref "MOD1") (pin "30") (pinfunction "SDA2_30") (pintype "bidirectional"))
    )
    (net (code "51") (name "unconnected-(MOD1-TX1-Pad9)") (class "Default")
      (node (ref "MOD1") (pin "9") (pinfunction "TX1_9") (pintype "bidirectional"))
    )
    (net (code "52") (name "unconnected-(MOD1-TX2-Pad32)") (class "Default")
      (node (ref "MOD1") (pin "32") (pinfunction "TX2_32") (pintype "bidirectional"))
    )
  )
)
